# stairs_control_schematic.net
KiCad netlist of a schematic drawn in Altium Designer
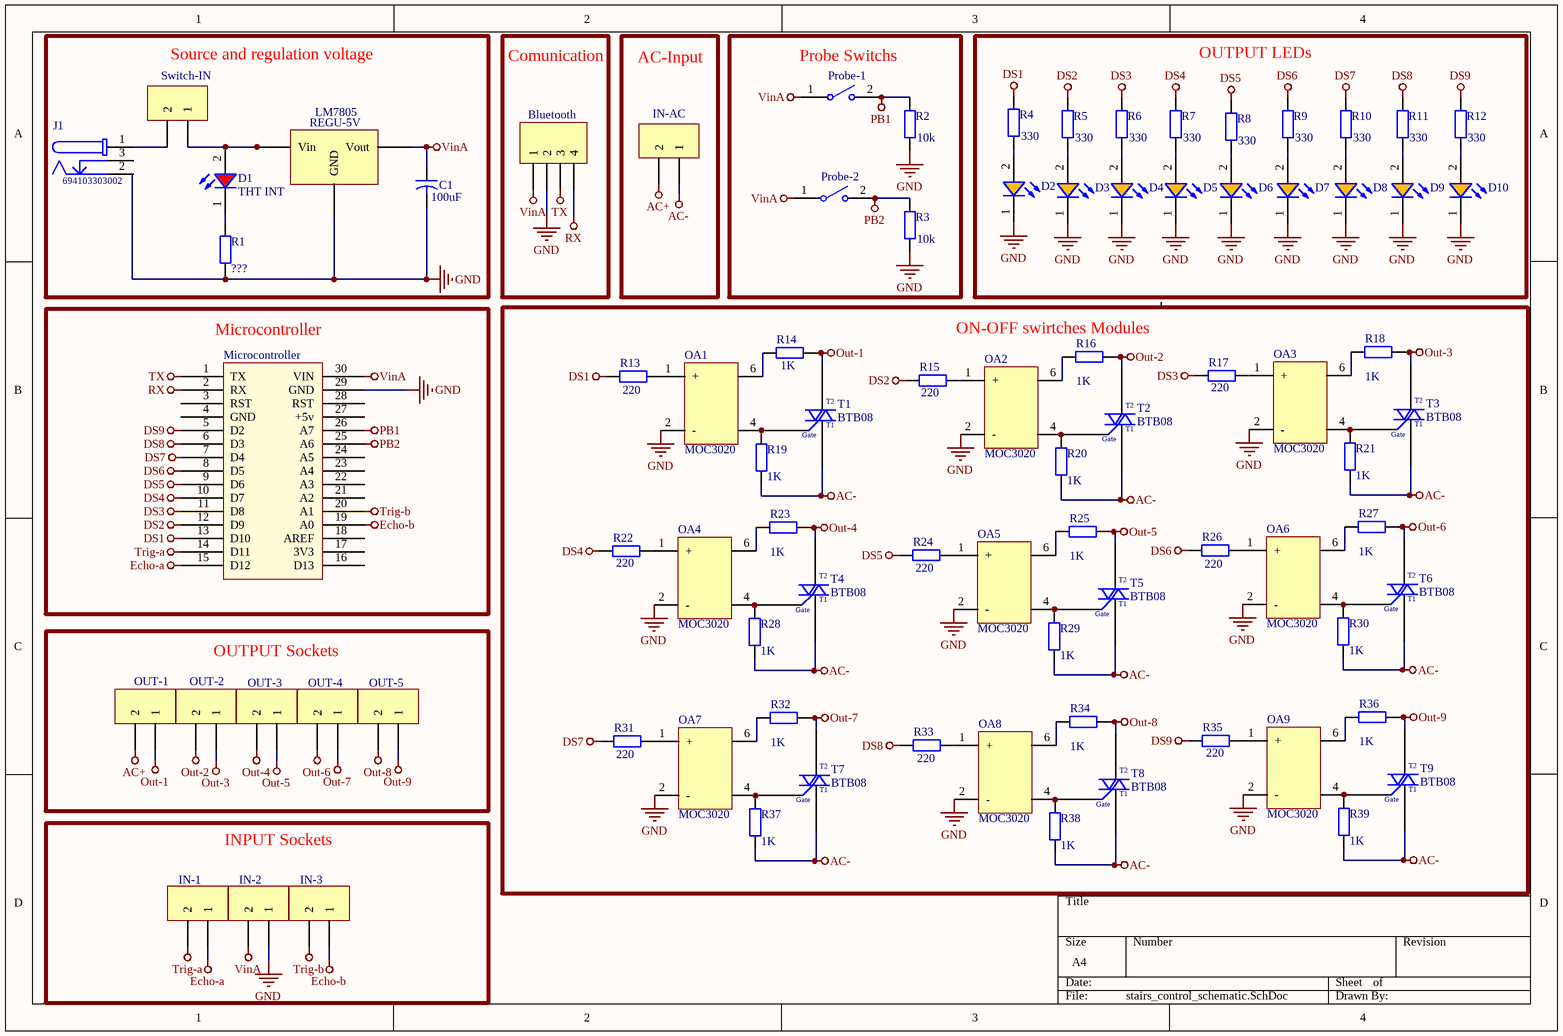
[diagram p0: stairs_control_schematic.SchDoc]

(export (version "E")
  (design (tool "Eeschema 10.0.6"))
  (components
    (comp (ref "Bluetooth")
      (value "Bluetooth")
      (footprint "HDR1X4")
      (description "Header, 4-Pin")
      (fields (field (name "PUBLISHER") "Altium Limited"))
      (libsource (lib "Miscellaneous Connectors") (part "Header 4"))
    )
    (comp (ref "C1")
      (value "100uF")
      (footprint "CAPR5-4X5")
      (description "Capacitor")
      (fields (field (name "PUBLISHER") "Altium Limited"))
      (libsource (lib "Miscellaneous Devices") (part "Cap2"))
    )
    (comp (ref "D1")
      (value "THT INT")
      (footprint "WL-TMRC_3mm")
      (description "WL-TMRC THT Mono-color Round Color, size 3mm, Super Red, 2V, 40deg")
      (fields (field (name "PART NUMBER") "151031SS04000") (field (name "PUBLISHER") "Wurth Elektronik"))
      (libsource (lib "LED THT") (part "151031SS04000"))
    )
    (comp (ref "D2")
      (value "SMD")
      (footprint "WL-SMCW_0603_H=0.7mm")
      (description "WL-SMCW SMT Mono-color Chip LED Waterclear, size 0603, Amber, 2V, 140deg")
      (fields (field (name "PART NUMBER") "150060AS75000") (field (name "PUBLISHER") "Wurth Elektronik"))
      (libsource (lib "LED'sSMD") (part "150060AS75000"))
    )
    (comp (ref "D3")
      (value "SMD")
      (footprint "WL-SMCW_0603_H=0.7mm")
      (description "WL-SMCW SMT Mono-color Chip LED Waterclear, size 0603, Amber, 2V, 140deg")
      (fields (field (name "PART NUMBER") "150060AS75000") (field (name "PUBLISHER") "Wurth Elektronik"))
      (libsource (lib "LED'sSMD") (part "150060AS75000"))
    )
    (comp (ref "D4")
      (value "SMD")
      (footprint "WL-SMCW_0603_H=0.7mm")
      (description "WL-SMCW SMT Mono-color Chip LED Waterclear, size 0603, Amber, 2V, 140deg")
      (fields (field (name "PART NUMBER") "150060AS75000") (field (name "PUBLISHER") "Wurth Elektronik"))
      (libsource (lib "LED'sSMD") (part "150060AS75000"))
    )
    (comp (ref "D5")
      (value "SMD")
      (footprint "WL-SMCW_0603_H=0.7mm")
      (description "WL-SMCW SMT Mono-color Chip LED Waterclear, size 0603, Amber, 2V, 140deg")
      (fields (field (name "PART NUMBER") "150060AS75000") (field (name "PUBLISHER") "Wurth Elektronik"))
      (libsource (lib "LED'sSMD") (part "150060AS75000"))
    )
    (comp (ref "D6")
      (value "SMD")
      (footprint "WL-SMCW_0603_H=0.7mm")
      (description "WL-SMCW SMT Mono-color Chip LED Waterclear, size 0603, Amber, 2V, 140deg")
      (fields (field (name "PART NUMBER") "150060AS75000") (field (name "PUBLISHER") "Wurth Elektronik"))
      (libsource (lib "LED'sSMD") (part "150060AS75000"))
    )
    (comp (ref "D7")
      (value "SMD")
      (footprint "WL-SMCW_0603_H=0.7mm")
      (description "WL-SMCW SMT Mono-color Chip LED Waterclear, size 0603, Amber, 2V, 140deg")
      (fields (field (name "PART NUMBER") "150060AS75000") (field (name "PUBLISHER") "Wurth Elektronik"))
      (libsource (lib "LED'sSMD") (part "150060AS75000"))
    )
    (comp (ref "D8")
      (value "SMD")
      (footprint "WL-SMCW_0603_H=0.7mm")
      (description "WL-SMCW SMT Mono-color Chip LED Waterclear, size 0603, Amber, 2V, 140deg")
      (fields (field (name "PART NUMBER") "150060AS75000") (field (name "PUBLISHER") "Wurth Elektronik"))
      (libsource (lib "LED'sSMD") (part "150060AS75000"))
    )
    (comp (ref "D9")
      (value "SMD")
      (footprint "WL-SMCW_0603_H=0.7mm")
      (description "WL-SMCW SMT Mono-color Chip LED Waterclear, size 0603, Amber, 2V, 140deg")
      (fields (field (name "PART NUMBER") "150060AS75000") (field (name "PUBLISHER") "Wurth Elektronik"))
      (libsource (lib "LED'sSMD") (part "150060AS75000"))
    )
    (comp (ref "D10")
      (value "SMD")
      (footprint "WL-SMCW_0603_H=0.7mm")
      (description "WL-SMCW SMT Mono-color Chip LED Waterclear, size 0603, Amber, 2V, 140deg")
      (fields (field (name "PART NUMBER") "150060AS75000") (field (name "PUBLISHER") "Wurth Elektronik"))
      (libsource (lib "LED'sSMD") (part "150060AS75000"))
    )
    (comp (ref "IN-1")
      (value "Terminal Block 2")
      (footprint "Terminal Block 2")
      (libsource (lib "Patrick's Library") (part "TB2"))
    )
    (comp (ref "IN-2")
      (value "Terminal Block 2")
      (footprint "Terminal Block 2")
      (libsource (lib "Patrick's Library") (part "TB2"))
    )
    (comp (ref "IN-3")
      (value "Terminal Block 2")
      (footprint "Terminal Block 2")
      (libsource (lib "Patrick's Library") (part "TB2"))
    )
    (comp (ref "IN-AC")
      (value "Terminal Block 2")
      (footprint "Terminal Block 2")
      (libsource (lib "Patrick's Library") (part "TB2"))
    )
    (comp (ref "J1")
      (value "694103303002")
      (footprint "694103303002")
      (description "DC Power Jack Connector WR-DC, Male, Right Angled, THT, 2 A, 30 V")
      (fields (field (name "PUBLISHER") "Wurth Elektronik"))
      (libsource (lib "DC_POWER_JACK_CONNECTORS_rev18b") (part "694103303002"))
    )
    (comp (ref "Microcontroller")
      (value "ArduinoNano")
      (footprint "ArduinoNano")
      (description "Arduino nano chino")
      (libsource (lib "Patrick's Library") (part "ArduinoNano"))
    )
    (comp (ref "OA1")
      (value "MOC3020")
      (footprint "PCBComponent_1")
      (libsource (lib "Patrick's Library") (part "MOC3020"))
    )
    (comp (ref "OA2")
      (value "MOC3020")
      (footprint "PCBComponent_1")
      (libsource (lib "Patrick's Library") (part "MOC3020"))
    )
    (comp (ref "OA3")
      (value "MOC3020")
      (footprint "PCBComponent_1")
      (libsource (lib "Patrick's Library") (part "MOC3020"))
    )
    (comp (ref "OA4")
      (value "MOC3020")
      (footprint "PCBComponent_1")
      (libsource (lib "Patrick's Library") (part "MOC3020"))
    )
    (comp (ref "OA5")
      (value "MOC3020")
      (footprint "PCBComponent_1")
      (libsource (lib "Patrick's Library") (part "MOC3020"))
    )
    (comp (ref "OA6")
      (value "MOC3020")
      (footprint "PCBComponent_1")
      (libsource (lib "Patrick's Library") (part "MOC3020"))
    )
    (comp (ref "OA7")
      (value "MOC3020")
      (footprint "PCBComponent_1")
      (libsource (lib "Patrick's Library") (part "MOC3020"))
    )
    (comp (ref "OA8")
      (value "MOC3020")
      (footprint "PCBComponent_1")
      (libsource (lib "Patrick's Library") (part "MOC3020"))
    )
    (comp (ref "OA9")
      (value "MOC3020")
      (footprint "PCBComponent_1")
      (libsource (lib "Patrick's Library") (part "MOC3020"))
    )
    (comp (ref "OUT-1")
      (value "Terminal Block 2")
      (footprint "Terminal Block 2")
      (libsource (lib "Patrick's Library") (part "TB2"))
    )
    (comp (ref "OUT-2")
      (value "Terminal Block 2")
      (footprint "Terminal Block 2")
      (libsource (lib "Patrick's Library") (part "TB2"))
    )
    (comp (ref "OUT-3")
      (value "Terminal Block 2")
      (footprint "Terminal Block 2")
      (libsource (lib "Patrick's Library") (part "TB2"))
    )
    (comp (ref "OUT-4")
      (value "Terminal Block 2")
      (footprint "Terminal Block 2")
      (libsource (lib "Patrick's Library") (part "TB2"))
    )
    (comp (ref "OUT-5")
      (value "Terminal Block 2")
      (footprint "Terminal Block 2")
      (libsource (lib "Patrick's Library") (part "TB2"))
    )
    (comp (ref "Probe-1")
      (value "Probe-1")
      (footprint "434111043826")
      (description "WS-TASV SMT Tact Switch 6x3.5mm, height 4.3mm, 260gf")
      (fields (field (name "PART NUMBER") "434111043826") (field (name "PUBLISHER") "Wurth Elektronik"))
      (libsource (lib "Switch SMD") (part "434111043826"))
    )
    (comp (ref "Probe-2")
      (value "Probre-2")
      (footprint "434111043826")
      (description "WS-TASV SMT Tact Switch 6x3.5mm, height 4.3mm, 260gf")
      (fields (field (name "PART NUMBER") "434111043826") (field (name "PUBLISHER") "Wurth Elektronik"))
      (libsource (lib "Switch SMD") (part "434111043826"))
    )
    (comp (ref "R1")
      (value "???")
      (footprint "AXIAL-0.4")
      (description "Resistor")
      (fields (field (name "Comment") "Res2") (field (name "PUBLISHER") "Altium Limited"))
      (libsource (lib "Miscellaneous Devices") (part "Res2"))
    )
    (comp (ref "R2")
      (value "10k")
      (footprint "WRIS-KSKE_0805_H=0.6mm")
      (description "WRIS-KSKE Thick Film Resistors, size 0805, 0.1Ohm, +/-1%, 0.33W")
      (fields (field (name "PART NUMBER") "560050320001") (field (name "PUBLISHER") "Wurth Elektronik"))
      (libsource (lib "Resistors SMD") (part "560050320001"))
    )
    (comp (ref "R3")
      (value "10k")
      (footprint "WRIS-KSKE_0805_H=0.6mm")
      (description "WRIS-KSKE Thick Film Resistors, size 0805, 0.1Ohm, +/-1%, 0.33W")
      (fields (field (name "PART NUMBER") "560050320001") (field (name "PUBLISHER") "Wurth Elektronik"))
      (libsource (lib "Resistors SMD") (part "560050320001"))
    )
    (comp (ref "R4")
      (value "330")
      (footprint "WRIS-KSKE_0805_H=0.6mm")
      (description "WRIS-KSKE Thick Film Resistors, size 0805, 0.1Ohm, +/-1%, 0.33W")
      (fields (field (name "PART NUMBER") "560050320001") (field (name "PUBLISHER") "Wurth Elektronik"))
      (libsource (lib "Resistors SMD") (part "560050320001"))
    )
    (comp (ref "R5")
      (value "330")
      (footprint "WRIS-KSKE_0805_H=0.6mm")
      (description "WRIS-KSKE Thick Film Resistors, size 0805, 0.1Ohm, +/-1%, 0.33W")
      (fields (field (name "PART NUMBER") "560050320001") (field (name "PUBLISHER") "Wurth Elektronik"))
      (libsource (lib "Resistors SMD") (part "560050320001"))
    )
    (comp (ref "R6")
      (value "330")
      (footprint "WRIS-KSKE_0805_H=0.6mm")
      (description "WRIS-KSKE Thick Film Resistors, size 0805, 0.1Ohm, +/-1%, 0.33W")
      (fields (field (name "PART NUMBER") "560050320001") (field (name "PUBLISHER") "Wurth Elektronik"))
      (libsource (lib "Resistors SMD") (part "560050320001"))
    )
    (comp (ref "R7")
      (value "330")
      (footprint "WRIS-KSKE_0805_H=0.6mm")
      (description "WRIS-KSKE Thick Film Resistors, size 0805, 0.1Ohm, +/-1%, 0.33W")
      (fields (field (name "PART NUMBER") "560050320001") (field (name "PUBLISHER") "Wurth Elektronik"))
      (libsource (lib "Resistors SMD") (part "560050320001"))
    )
    (comp (ref "R8")
      (value "330")
      (footprint "WRIS-KSKE_0805_H=0.6mm")
      (description "WRIS-KSKE Thick Film Resistors, size 0805, 0.1Ohm, +/-1%, 0.33W")
      (fields (field (name "PART NUMBER") "560050320001") (field (name "PUBLISHER") "Wurth Elektronik"))
      (libsource (lib "Resistors SMD") (part "560050320001"))
    )
    (comp (ref "R9")
      (value "330")
      (footprint "WRIS-KSKE_0805_H=0.6mm")
      (description "WRIS-KSKE Thick Film Resistors, size 0805, 0.1Ohm, +/-1%, 0.33W")
      (fields (field (name "PART NUMBER") "560050320001") (field (name "PUBLISHER") "Wurth Elektronik"))
      (libsource (lib "Resistors SMD") (part "560050320001"))
    )
    (comp (ref "R10")
      (value "330")
      (footprint "WRIS-KSKE_0805_H=0.6mm")
      (description "WRIS-KSKE Thick Film Resistors, size 0805, 0.1Ohm, +/-1%, 0.33W")
      (fields (field (name "PART NUMBER") "560050320001") (field (name "PUBLISHER") "Wurth Elektronik"))
      (libsource (lib "Resistors SMD") (part "560050320001"))
    )
    (comp (ref "R11")
      (value "330")
      (footprint "WRIS-KSKE_0805_H=0.6mm")
      (description "WRIS-KSKE Thick Film Resistors, size 0805, 0.1Ohm, +/-1%, 0.33W")
      (fields (field (name "PART NUMBER") "560050320001") (field (name "PUBLISHER") "Wurth Elektronik"))
      (libsource (lib "Resistors SMD") (part "560050320001"))
    )
    (comp (ref "R12")
      (value "330")
      (footprint "WRIS-KSKE_0805_H=0.6mm")
      (description "WRIS-KSKE Thick Film Resistors, size 0805, 0.1Ohm, +/-1%, 0.33W")
      (fields (field (name "PART NUMBER") "560050320001") (field (name "PUBLISHER") "Wurth Elektronik"))
      (libsource (lib "Resistors SMD") (part "560050320001"))
    )
    (comp (ref "R13")
      (value "220")
      (footprint "AXIAL-0.4")
      (description "Resistor")
      (fields (field (name "Comment") "Res2") (field (name "PUBLISHER") "Altium Limited"))
      (libsource (lib "") (part "Res2_1"))
    )
    (comp (ref "R14")
      (value "1K")
      (footprint "AXIAL-0.4")
      (description "Resistor")
      (fields (field (name "Comment") "Res2") (field (name "PUBLISHER") "Altium Limited"))
      (libsource (lib "") (part "Res2_2"))
    )
    (comp (ref "R15")
      (value "220")
      (footprint "AXIAL-0.4")
      (description "Resistor")
      (fields (field (name "Comment") "Res2") (field (name "PUBLISHER") "Altium Limited"))
      (libsource (lib "") (part "Res2_1"))
    )
    (comp (ref "R16")
      (value "1K")
      (footprint "AXIAL-0.4")
      (description "Resistor")
      (fields (field (name "Comment") "Res2") (field (name "PUBLISHER") "Altium Limited"))
      (libsource (lib "") (part "Res2_2"))
    )
    (comp (ref "R17")
      (value "220")
      (footprint "AXIAL-0.4")
      (description "Resistor")
      (fields (field (name "Comment") "Res2") (field (name "PUBLISHER") "Altium Limited"))
      (libsource (lib "") (part "Res2_1"))
    )
    (comp (ref "R18")
      (value "1K")
      (footprint "AXIAL-0.4")
      (description "Resistor")
      (fields (field (name "Comment") "Res2") (field (name "PUBLISHER") "Altium Limited"))
      (libsource (lib "") (part "Res2_2"))
    )
    (comp (ref "R19")
      (value "1K")
      (footprint "AXIAL-0.4")
      (description "Resistor")
      (fields (field (name "Comment") "Res2") (field (name "PUBLISHER") "Altium Limited"))
      (libsource (lib "Miscellaneous Devices") (part "Res2"))
    )
    (comp (ref "R20")
      (value "1K")
      (footprint "AXIAL-0.4")
      (description "Resistor")
      (fields (field (name "Comment") "Res2") (field (name "PUBLISHER") "Altium Limited"))
      (libsource (lib "Miscellaneous Devices") (part "Res2"))
    )
    (comp (ref "R21")
      (value "1K")
      (footprint "AXIAL-0.4")
      (description "Resistor")
      (fields (field (name "Comment") "Res2") (field (name "PUBLISHER") "Altium Limited"))
      (libsource (lib "Miscellaneous Devices") (part "Res2"))
    )
    (comp (ref "R22")
      (value "220")
      (footprint "AXIAL-0.4")
      (description "Resistor")
      (fields (field (name "Comment") "Res2") (field (name "PUBLISHER") "Altium Limited"))
      (libsource (lib "") (part "Res2_1"))
    )
    (comp (ref "R23")
      (value "1K")
      (footprint "AXIAL-0.4")
      (description "Resistor")
      (fields (field (name "Comment") "Res2") (field (name "PUBLISHER") "Altium Limited"))
      (libsource (lib "") (part "Res2_2"))
    )
    (comp (ref "R24")
      (value "220")
      (footprint "AXIAL-0.4")
      (description "Resistor")
      (fields (field (name "Comment") "Res2") (field (name "PUBLISHER") "Altium Limited"))
      (libsource (lib "") (part "Res2_1"))
    )
    (comp (ref "R25")
      (value "1K")
      (footprint "AXIAL-0.4")
      (description "Resistor")
      (fields (field (name "Comment") "Res2") (field (name "PUBLISHER") "Altium Limited"))
      (libsource (lib "") (part "Res2_2"))
    )
    (comp (ref "R26")
      (value "220")
      (footprint "AXIAL-0.4")
      (description "Resistor")
      (fields (field (name "Comment") "Res2") (field (name "PUBLISHER") "Altium Limited"))
      (libsource (lib "") (part "Res2_1"))
    )
    (comp (ref "R27")
      (value "1K")
      (footprint "AXIAL-0.4")
      (description "Resistor")
      (fields (field (name "Comment") "Res2") (field (name "PUBLISHER") "Altium Limited"))
      (libsource (lib "") (part "Res2_2"))
    )
    (comp (ref "R28")
      (value "1K")
      (footprint "AXIAL-0.4")
      (description "Resistor")
      (fields (field (name "Comment") "Res2") (field (name "PUBLISHER") "Altium Limited"))
      (libsource (lib "Miscellaneous Devices") (part "Res2"))
    )
    (comp (ref "R29")
      (value "1K")
      (footprint "AXIAL-0.4")
      (description "Resistor")
      (fields (field (name "Comment") "Res2") (field (name "PUBLISHER") "Altium Limited"))
      (libsource (lib "Miscellaneous Devices") (part "Res2"))
    )
    (comp (ref "R30")
      (value "1K")
      (footprint "AXIAL-0.4")
      (description "Resistor")
      (fields (field (name "Comment") "Res2") (field (name "PUBLISHER") "Altium Limited"))
      (libsource (lib "Miscellaneous Devices") (part "Res2"))
    )
    (comp (ref "R31")
      (value "220")
      (footprint "AXIAL-0.4")
      (description "Resistor")
      (fields (field (name "Comment") "Res2") (field (name "PUBLISHER") "Altium Limited"))
      (libsource (lib "") (part "Res2_1"))
    )
    (comp (ref "R32")
      (value "1K")
      (footprint "AXIAL-0.4")
      (description "Resistor")
      (fields (field (name "Comment") "Res2") (field (name "PUBLISHER") "Altium Limited"))
      (libsource (lib "") (part "Res2_2"))
    )
    (comp (ref "R33")
      (value "220")
      (footprint "AXIAL-0.4")
      (description "Resistor")
      (fields (field (name "Comment") "Res2") (field (name "PUBLISHER") "Altium Limited"))
      (libsource (lib "") (part "Res2_1"))
    )
    (comp (ref "R34")
      (value "1K")
      (footprint "AXIAL-0.4")
      (description "Resistor")
      (fields (field (name "Comment") "Res2") (field (name "PUBLISHER") "Altium Limited"))
      (libsource (lib "") (part "Res2_2"))
    )
    (comp (ref "R35")
      (value "220")
      (footprint "AXIAL-0.4")
      (description "Resistor")
      (fields (field (name "Comment") "Res2") (field (name "PUBLISHER") "Altium Limited"))
      (libsource (lib "") (part "Res2_1"))
    )
    (comp (ref "R36")
      (value "1K")
      (footprint "AXIAL-0.4")
      (description "Resistor")
      (fields (field (name "Comment") "Res2") (field (name "PUBLISHER") "Altium Limited"))
      (libsource (lib "") (part "Res2_2"))
    )
    (comp (ref "R37")
      (value "1K")
      (footprint "AXIAL-0.4")
      (description "Resistor")
      (fields (field (name "Comment") "Res2") (field (name "PUBLISHER") "Altium Limited"))
      (libsource (lib "Miscellaneous Devices") (part "Res2"))
    )
    (comp (ref "R38")
      (value "1K")
      (footprint "AXIAL-0.4")
      (description "Resistor")
      (fields (field (name "Comment") "Res2") (field (name "PUBLISHER") "Altium Limited"))
      (libsource (lib "Miscellaneous Devices") (part "Res2"))
    )
    (comp (ref "R39")
      (value "1K")
      (footprint "AXIAL-0.4")
      (description "Resistor")
      (fields (field (name "Comment") "Res2") (field (name "PUBLISHER") "Altium Limited"))
      (libsource (lib "Miscellaneous Devices") (part "Res2"))
    )
    (comp (ref "REGU-5V")
      (value "LM7805")
      (footprint "LM7805")
      (libsource (lib "Patrick's Library") (part "LM7805"))
    )
    (comp (ref "Switch-IN")
      (value "Terminal Block 2")
      (footprint "Terminal Block 2")
      (libsource (lib "Patrick's Library") (part "TB2"))
    )
    (comp (ref "T1")
      (value "BTB08")
      (footprint "LM7805")
      (libsource (lib "Patrick's Library") (part "BTB08"))
    )
    (comp (ref "T2")
      (value "BTB08")
      (footprint "LM7805")
      (libsource (lib "Patrick's Library") (part "BTB08"))
    )
    (comp (ref "T3")
      (value "BTB08")
      (footprint "LM7805")
      (libsource (lib "Patrick's Library") (part "BTB08"))
    )
    (comp (ref "T4")
      (value "BTB08")
      (footprint "LM7805")
      (libsource (lib "Patrick's Library") (part "BTB08"))
    )
    (comp (ref "T5")
      (value "BTB08")
      (footprint "LM7805")
      (libsource (lib "Patrick's Library") (part "BTB08"))
    )
    (comp (ref "T6")
      (value "BTB08")
      (footprint "LM7805")
      (libsource (lib "Patrick's Library") (part "BTB08"))
    )
    (comp (ref "T7")
      (value "BTB08")
      (footprint "LM7805")
      (libsource (lib "Patrick's Library") (part "BTB08"))
    )
    (comp (ref "T8")
      (value "BTB08")
      (footprint "LM7805")
      (libsource (lib "Patrick's Library") (part "BTB08"))
    )
    (comp (ref "T9")
      (value "BTB08")
      (footprint "LM7805")
      (libsource (lib "Patrick's Library") (part "BTB08"))
    )
  )
  (nets
    (net (code "1") (name "AC+") (class "Default")
      (node (ref "IN-AC") (pin "2") (pinfunction "2_2") (pintype "passive"))
      (node (ref "OUT-1") (pin "2") (pinfunction "2_2") (pintype "passive"))
    )
    (net (code "2") (name "AC-") (class "Default")
      (node (ref "IN-AC") (pin "1") (pinfunction "1_1") (pintype "passive"))
      (node (ref "R19") (pin "1") (pinfunction "1_1") (pintype "passive"))
      (node (ref "R20") (pin "1") (pinfunction "1_1") (pintype "passive"))
      (node (ref "R21") (pin "1") (pinfunction "1_1") (pintype "passive"))
      (node (ref "R28") (pin "1") (pinfunction "1_1") (pintype "passive"))
      (node (ref "R29") (pin "1") (pinfunction "1_1") (pintype "passive"))
      (node (ref "R30") (pin "1") (pinfunction "1_1") (pintype "passive"))
      (node (ref "R37") (pin "1") (pinfunction "1_1") (pintype "passive"))
      (node (ref "R38") (pin "1") (pinfunction "1_1") (pintype "passive"))
      (node (ref "R39") (pin "1") (pinfunction "1_1") (pintype "passive"))
      (node (ref "T1") (pin "1") (pinfunction "T1_1") (pintype "passive"))
      (node (ref "T2") (pin "1") (pinfunction "T1_1") (pintype "passive"))
      (node (ref "T3") (pin "1") (pinfunction "T1_1") (pintype "passive"))
      (node (ref "T4") (pin "1") (pinfunction "T1_1") (pintype "passive"))
      (node (ref "T5") (pin "1") (pinfunction "T1_1") (pintype "passive"))
      (node (ref "T6") (pin "1") (pinfunction "T1_1") (pintype "passive"))
      (node (ref "T7") (pin "1") (pinfunction "T1_1") (pintype "passive"))
      (node (ref "T8") (pin "1") (pinfunction "T1_1") (pintype "passive"))
      (node (ref "T9") (pin "1") (pinfunction "T1_1") (pintype "passive"))
    )
    (net (code "3") (name "DS1") (class "Default")
      (node (ref "Microcontroller") (pin "13") (pinfunction "D10_13") (pintype "passive"))
      (node (ref "R13") (pin "2") (pinfunction "2_2") (pintype "passive"))
      (node (ref "R4") (pin "2") (pinfunction "2_2") (pintype "passive"))
    )
    (net (code "4") (name "DS2") (class "Default")
      (node (ref "Microcontroller") (pin "12") (pinfunction "D9_12") (pintype "passive"))
      (node (ref "R15") (pin "2") (pinfunction "2_2") (pintype "passive"))
      (node (ref "R5") (pin "2") (pinfunction "2_2") (pintype "passive"))
    )
    (net (code "5") (name "DS3") (class "Default")
      (node (ref "Microcontroller") (pin "11") (pinfunction "D8_11") (pintype "passive"))
      (node (ref "R17") (pin "2") (pinfunction "2_2") (pintype "passive"))
      (node (ref "R6") (pin "2") (pinfunction "2_2") (pintype "passive"))
    )
    (net (code "6") (name "DS4") (class "Default")
      (node (ref "Microcontroller") (pin "10") (pinfunction "D7_10") (pintype "passive"))
      (node (ref "R22") (pin "2") (pinfunction "2_2") (pintype "passive"))
      (node (ref "R7") (pin "2") (pinfunction "2_2") (pintype "passive"))
    )
    (net (code "7") (name "DS5") (class "Default")
      (node (ref "Microcontroller") (pin "9") (pinfunction "D6_9") (pintype "passive"))
      (node (ref "R24") (pin "2") (pinfunction "2_2") (pintype "passive"))
      (node (ref "R8") (pin "2") (pinfunction "2_2") (pintype "passive"))
    )
    (net (code "8") (name "DS6") (class "Default")
      (node (ref "Microcontroller") (pin "8") (pinfunction "D5_8") (pintype "passive"))
      (node (ref "R26") (pin "2") (pinfunction "2_2") (pintype "passive"))
      (node (ref "R9") (pin "2") (pinfunction "2_2") (pintype "passive"))
    )
    (net (code "9") (name "DS7") (class "Default")
      (node (ref "Microcontroller") (pin "7") (pinfunction "D4_7") (pintype "passive"))
      (node (ref "R10") (pin "2") (pinfunction "2_2") (pintype "passive"))
      (node (ref "R31") (pin "2") (pinfunction "2_2") (pintype "passive"))
    )
    (net (code "10") (name "DS8") (class "Default")
      (node (ref "Microcontroller") (pin "6") (pinfunction "D3_6") (pintype "passive"))
      (node (ref "R11") (pin "2") (pinfunction "2_2") (pintype "passive"))
      (node (ref "R33") (pin "2") (pinfunction "2_2") (pintype "passive"))
    )
    (net (code "11") (name "DS9") (class "Default")
      (node (ref "Microcontroller") (pin "5") (pinfunction "D2_5") (pintype "passive"))
      (node (ref "R12") (pin "2") (pinfunction "2_2") (pintype "passive"))
      (node (ref "R35") (pin "2") (pinfunction "2_2") (pintype "passive"))
    )
    (net (code "12") (name "Echo-a") (class "Default")
      (node (ref "IN-1") (pin "1") (pinfunction "1_1") (pintype "passive"))
      (node (ref "Microcontroller") (pin "15") (pinfunction "D12_15") (pintype "passive"))
    )
    (net (code "13") (name "Echo-b") (class "Default")
      (node (ref "IN-3") (pin "1") (pinfunction "1_1") (pintype "passive"))
      (node (ref "Microcontroller") (pin "19") (pinfunction "A0_19") (pintype "passive"))
    )
    (net (code "14") (name "GND") (class "Default")
      (node (ref "Bluetooth") (pin "2") (pinfunction "2_2") (pintype "passive"))
      (node (ref "C1") (pin "2") (pinfunction "2_2") (pintype "passive"))
      (node (ref "D10") (pin "1") (pinfunction "K_1") (pintype "passive"))
      (node (ref "D2") (pin "1") (pinfunction "K_1") (pintype "passive"))
      (node (ref "D3") (pin "1") (pinfunction "K_1") (pintype "passive"))
      (node (ref "D4") (pin "1") (pinfunction "K_1") (pintype "passive"))
      (node (ref "D5") (pin "1") (pinfunction "K_1") (pintype "passive"))
      (node (ref "D6") (pin "1") (pinfunction "K_1") (pintype "passive"))
      (node (ref "D7") (pin "1") (pinfunction "K_1") (pintype "passive"))
      (node (ref "D8") (pin "1") (pinfunction "K_1") (pintype "passive"))
      (node (ref "D9") (pin "1") (pinfunction "K_1") (pintype "passive"))
      (node (ref "IN-2") (pin "1") (pinfunction "1_1") (pintype "passive"))
      (node (ref "J1") (pin "2") (pinfunction "2_2") (pintype "passive"))
      (node (ref "Microcontroller") (pin "29") (pinfunction "GND_29") (pintype "passive"))
      (node (ref "OA1") (pin "2") (pinfunction "-_2") (pintype "passive"))
      (node (ref "OA2") (pin "2") (pinfunction "-_2") (pintype "passive"))
      (node (ref "OA3") (pin "2") (pinfunction "-_2") (pintype "passive"))
      (node (ref "OA4") (pin "2") (pinfunction "-_2") (pintype "passive"))
      (node (ref "OA5") (pin "2") (pinfunction "-_2") (pintype "passive"))
      (node (ref "OA6") (pin "2") (pinfunction "-_2") (pintype "passive"))
      (node (ref "OA7") (pin "2") (pinfunction "-_2") (pintype "passive"))
      (node (ref "OA8") (pin "2") (pinfunction "-_2") (pintype "passive"))
      (node (ref "OA9") (pin "2") (pinfunction "-_2") (pintype "passive"))
      (node (ref "R1") (pin "1") (pinfunction "1_1") (pintype "passive"))
      (node (ref "R2") (pin "1") (pinfunction "1_1") (pintype "passive"))
      (node (ref "R3") (pin "1") (pinfunction "1_1") (pintype "passive"))
      (node (ref "REGU-5V") (pin "2") (pinfunction "GND_2") (pintype "passive"))
    )
    (net (code "15") (name "Net-(D1-A)") (class "Default")
      (node (ref "D1") (pin "2") (pinfunction "A_2") (pintype "passive"))
      (node (ref "REGU-5V") (pin "1") (pinfunction "Vin_1") (pintype "passive"))
      (node (ref "Switch-IN") (pin "1") (pinfunction "1_1") (pintype "passive"))
    )
    (net (code "16") (name "Net-(D1-K)") (class "Default")
      (node (ref "D1") (pin "1") (pinfunction "K_1") (pintype "passive"))
      (node (ref "R1") (pin "2") (pinfunction "2_2") (pintype "passive"))
    )
    (net (code "17") (name "Net-(D2-A)") (class "Default")
      (node (ref "D2") (pin "2") (pinfunction "A_2") (pintype "passive"))
      (node (ref "R4") (pin "1") (pinfunction "1_1") (pintype "passive"))
    )
    (net (code "18") (name "Net-(D3-A)") (class "Default")
      (node (ref "D3") (pin "2") (pinfunction "A_2") (pintype "passive"))
      (node (ref "R5") (pin "1") (pinfunction "1_1") (pintype "passive"))
    )
    (net (code "19") (name "Net-(D4-A)") (class "Default")
      (node (ref "D4") (pin "2") (pinfunction "A_2") (pintype "passive"))
      (node (ref "R6") (pin "1") (pinfunction "1_1") (pintype "passive"))
    )
    (net (code "20") (name "Net-(D5-A)") (class "Default")
      (node (ref "D5") (pin "2") (pinfunction "A_2") (pintype "passive"))
      (node (ref "R7") (pin "1") (pinfunction "1_1") (pintype "passive"))
    )
    (net (code "21") (name "Net-(D6-A)") (class "Default")
      (node (ref "D6") (pin "2") (pinfunction "A_2") (pintype "passive"))
      (node (ref "R8") (pin "1") (pinfunction "1_1") (pintype "passive"))
    )
    (net (code "22") (name "Net-(D7-A)") (class "Default")
      (node (ref "D7") (pin "2") (pinfunction "A_2") (pintype "passive"))
      (node (ref "R9") (pin "1") (pinfunction "1_1") (pintype "passive"))
    )
    (net (code "23") (name "Net-(D8-A)") (class "Default")
      (node (ref "D8") (pin "2") (pinfunction "A_2") (pintype "passive"))
      (node (ref "R10") (pin "1") (pinfunction "1_1") (pintype "passive"))
    )
    (net (code "24") (name "Net-(D9-A)") (class "Default")
      (node (ref "D9") (pin "2") (pinfunction "A_2") (pintype "passive"))
      (node (ref "R11") (pin "1") (pinfunction "1_1") (pintype "passive"))
    )
    (net (code "25") (name "Net-(D10-A)") (class "Default")
      (node (ref "D10") (pin "2") (pinfunction "A_2") (pintype "passive"))
      (node (ref "R12") (pin "1") (pinfunction "1_1") (pintype "passive"))
    )
    (net (code "26") (name "Net-(J1-Pad1)") (class "Default")
      (node (ref "J1") (pin "1") (pinfunction "1_1") (pintype "passive"))
      (node (ref "Switch-IN") (pin "2") (pinfunction "2_2") (pintype "passive"))
    )
    (net (code "27") (name "Net-(OA1-+)") (class "Default")
      (node (ref "OA1") (pin "1") (pinfunction "+_1") (pintype "passive"))
      (node (ref "R13") (pin "1") (pinfunction "1_1") (pintype "passive"))
    )
    (net (code "28") (name "Net-(OA1-50)") (class "Default")
      (node (ref "OA1") (pin "4") (pinfunction "50_4") (pintype "passive"))
      (node (ref "R19") (pin "2") (pinfunction "2_2") (pintype "passive"))
      (node (ref "T1") (pin "3") (pinfunction "Gate_3") (pintype "passive"))
    )
    (net (code "29") (name "Net-(OA1-51)") (class "Default")
      (node (ref "OA1") (pin "6") (pinfunction "51_6") (pintype "passive"))
      (node (ref "R14") (pin "1") (pinfunction "1_1") (pintype "passive"))
    )
    (net (code "30") (name "Net-(OA2-+)") (class "Default")
      (node (ref "OA2") (pin "1") (pinfunction "+_1") (pintype "passive"))
      (node (ref "R15") (pin "1") (pinfunction "1_1") (pintype "passive"))
    )
    (net (code "31") (name "Net-(OA2-50)") (class "Default")
      (node (ref "OA2") (pin "4") (pinfunction "50_4") (pintype "passive"))
      (node (ref "R20") (pin "2") (pinfunction "2_2") (pintype "passive"))
      (node (ref "T2") (pin "3") (pinfunction "Gate_3") (pintype "passive"))
    )
    (net (code "32") (name "Net-(OA2-51)") (class "Default")
      (node (ref "OA2") (pin "6") (pinfunction "51_6") (pintype "passive"))
      (node (ref "R16") (pin "1") (pinfunction "1_1") (pintype "passive"))
    )
    (net (code "33") (name "Net-(OA3-+)") (class "Default")
      (node (ref "OA3") (pin "1") (pinfunction "+_1") (pintype "passive"))
      (node (ref "R17") (pin "1") (pinfunction "1_1") (pintype "passive"))
    )
    (net (code "34") (name "Net-(OA3-50)") (class "Default")
      (node (ref "OA3") (pin "4") (pinfunction "50_4") (pintype "passive"))
      (node (ref "R21") (pin "2") (pinfunction "2_2") (pintype "passive"))
      (node (ref "T3") (pin "3") (pinfunction "Gate_3") (pintype "passive"))
    )
    (net (code "35") (name "Net-(OA3-51)") (class "Default")
      (node (ref "OA3") (pin "6") (pinfunction "51_6") (pintype "passive"))
      (node (ref "R18") (pin "1") (pinfunction "1_1") (pintype "passive"))
    )
    (net (code "36") (name "Net-(OA4-+)") (class "Default")
      (node (ref "OA4") (pin "1") (pinfunction "+_1") (pintype "passive"))
      (node (ref "R22") (pin "1") (pinfunction "1_1") (pintype "passive"))
    )
    (net (code "37") (name "Net-(OA4-50)") (class "Default")
      (node (ref "OA4") (pin "4") (pinfunction "50_4") (pintype "passive"))
      (node (ref "R28") (pin "2") (pinfunction "2_2") (pintype "passive"))
      (node (ref "T4") (pin "3") (pinfunction "Gate_3") (pintype "passive"))
    )
    (net (code "38") (name "Net-(OA4-51)") (class "Default")
      (node (ref "OA4") (pin "6") (pinfunction "51_6") (pintype "passive"))
      (node (ref "R23") (pin "1") (pinfunction "1_1") (pintype "passive"))
    )
    (net (code "39") (name "Net-(OA5-+)") (class "Default")
      (node (ref "OA5") (pin "1") (pinfunction "+_1") (pintype "passive"))
      (node (ref "R24") (pin "1") (pinfunction "1_1") (pintype "passive"))
    )
    (net (code "40") (name "Net-(OA5-50)") (class "Default")
      (node (ref "OA5") (pin "4") (pinfunction "50_4") (pintype "passive"))
      (node (ref "R29") (pin "2") (pinfunction "2_2") (pintype "passive"))
      (node (ref "T5") (pin "3") (pinfunction "Gate_3") (pintype "passive"))
    )
    (net (code "41") (name "Net-(OA5-51)") (class "Default")
      (node (ref "OA5") (pin "6") (pinfunction "51_6") (pintype "passive"))
      (node (ref "R25") (pin "1") (pinfunction "1_1") (pintype "passive"))
    )
    (net (code "42") (name "Net-(OA6-+)") (class "Default")
      (node (ref "OA6") (pin "1") (pinfunction "+_1") (pintype "passive"))
      (node (ref "R26") (pin "1") (pinfunction "1_1") (pintype "passive"))
    )
    (net (code "43") (name "Net-(OA6-50)") (class "Default")
      (node (ref "OA6") (pin "4") (pinfunction "50_4") (pintype "passive"))
      (node (ref "R30") (pin "2") (pinfunction "2_2") (pintype "passive"))
      (node (ref "T6") (pin "3") (pinfunction "Gate_3") (pintype "passive"))
    )
    (net (code "44") (name "Net-(OA6-51)") (class "Default")
      (node (ref "OA6") (pin "6") (pinfunction "51_6") (pintype "passive"))
      (node (ref "R27") (pin "1") (pinfunction "1_1") (pintype "passive"))
    )
    (net (code "45") (name "Net-(OA7-+)") (class "Default")
      (node (ref "OA7") (pin "1") (pinfunction "+_1") (pintype "passive"))
      (node (ref "R31") (pin "1") (pinfunction "1_1") (pintype "passive"))
    )
    (net (code "46") (name "Net-(OA7-50)") (class "Default")
      (node (ref "OA7") (pin "4") (pinfunction "50_4") (pintype "passive"))
      (node (ref "R37") (pin "2") (pinfunction "2_2") (pintype "passive"))
      (node (ref "T7") (pin "3") (pinfunction "Gate_3") (pintype "passive"))
    )
    (net (code "47") (name "Net-(OA7-51)") (class "Default")
      (node (ref "OA7") (pin "6") (pinfunction "51_6") (pintype "passive"))
      (node (ref "R32") (pin "1") (pinfunction "1_1") (pintype "passive"))
    )
    (net (code "48") (name "Net-(OA8-+)") (class "Default")
      (node (ref "OA8") (pin "1") (pinfunction "+_1") (pintype "passive"))
      (node (ref "R33") (pin "1") (pinfunction "1_1") (pintype "passive"))
    )
    (net (code "49") (name "Net-(OA8-50)") (class "Default")
      (node (ref "OA8") (pin "4") (pinfunction "50_4") (pintype "passive"))
      (node (ref "R38") (pin "2") (pinfunction "2_2") (pintype "passive"))
      (node (ref "T8") (pin "3") (pinfunction "Gate_3") (pintype "passive"))
    )
    (net (code "50") (name "Net-(OA8-51)") (class "Default")
      (node (ref "OA8") (pin "6") (pinfunction "51_6") (pintype "passive"))
      (node (ref "R34") (pin "1") (pinfunction "1_1") (pintype "passive"))
    )
    (net (code "51") (name "Net-(OA9-+)") (class "Default")
      (node (ref "OA9") (pin "1") (pinfunction "+_1") (pintype "passive"))
      (node (ref "R35") (pin "1") (pinfunction "1_1") (pintype "passive"))
    )
    (net (code "52") (name "Net-(OA9-50)") (class "Default")
      (node (ref "OA9") (pin "4") (pinfunction "50_4") (pintype "passive"))
      (node (ref "R39") (pin "2") (pinfunction "2_2") (pintype "passive"))
      (node (ref "T9") (pin "3") (pinfunction "Gate_3") (pintype "passive"))
    )
    (net (code "53") (name "Net-(OA9-51)") (class "Default")
      (node (ref "OA9") (pin "6") (pinfunction "51_6") (pintype "passive"))
      (node (ref "R36") (pin "1") (pinfunction "1_1") (pintype "passive"))
    )
    (net (code "54") (name "Out-1") (class "Default")
      (node (ref "OUT-1") (pin "1") (pinfunction "1_1") (pintype "passive"))
      (node (ref "R14") (pin "2") (pinfunction "2_2") (pintype "passive"))
      (node (ref "T1") (pin "2") (pinfunction "T2_2") (pintype "passive"))
    )
    (net (code "55") (name "Out-2") (class "Default")
      (node (ref "OUT-2") (pin "2") (pinfunction "2_2") (pintype "passive"))
      (node (ref "R16") (pin "2") (pinfunction "2_2") (pintype "passive"))
      (node (ref "T2") (pin "2") (pinfunction "T2_2") (pintype "passive"))
    )
    (net (code "56") (name "Out-3") (class "Default")
      (node (ref "OUT-2") (pin "1") (pinfunction "1_1") (pintype "passive"))
      (node (ref "R18") (pin "2") (pinfunction "2_2") (pintype "passive"))
      (node (ref "T3") (pin "2") (pinfunction "T2_2") (pintype "passive"))
    )
    (net (code "57") (name "Out-4") (class "Default")
      (node (ref "OUT-3") (pin "2") (pinfunction "2_2") (pintype "passive"))
      (node (ref "R23") (pin "2") (pinfunction "2_2") (pintype "passive"))
      (node (ref "T4") (pin "2") (pinfunction "T2_2") (pintype "passive"))
    )
    (net (code "58") (name "Out-5") (class "Default")
      (node (ref "OUT-3") (pin "1") (pinfunction "1_1") (pintype "passive"))
      (node (ref "R25") (pin "2") (pinfunction "2_2") (pintype "passive"))
      (node (ref "T5") (pin "2") (pinfunction "T2_2") (pintype "passive"))
    )
    (net (code "59") (name "Out-6") (class "Default")
      (node (ref "OUT-4") (pin "2") (pinfunction "2_2") (pintype "passive"))
      (node (ref "R27") (pin "2") (pinfunction "2_2") (pintype "passive"))
      (node (ref "T6") (pin "2") (pinfunction "T2_2") (pintype "passive"))
    )
    (net (code "60") (name "Out-7") (class "Default")
      (node (ref "OUT-4") (pin "1") (pinfunction "1_1") (pintype "passive"))
      (node (ref "R32") (pin "2") (pinfunction "2_2") (pintype "passive"))
      (node (ref "T7") (pin "2") (pinfunction "T2_2") (pintype "passive"))
    )
    (net (code "61") (name "Out-8") (class "Default")
      (node (ref "OUT-5") (pin "2") (pinfunction "2_2") (pintype "passive"))
      (node (ref "R34") (pin "2") (pinfunction "2_2") (pintype "passive"))
      (node (ref "T8") (pin "2") (pinfunction "T2_2") (pintype "passive"))
    )
    (net (code "62") (name "Out-9") (class "Default")
      (node (ref "OUT-5") (pin "1") (pinfunction "1_1") (pintype "passive"))
      (node (ref "R36") (pin "2") (pinfunction "2_2") (pintype "passive"))
      (node (ref "T9") (pin "2") (pinfunction "T2_2") (pintype "passive"))
    )
    (net (code "63") (name "PB1") (class "Default")
      (node (ref "Microcontroller") (pin "26") (pinfunction "A7_26") (pintype "passive"))
      (node (ref "Probe-1") (pin "2") (pinfunction "2_2") (pintype "passive"))
      (node (ref "R2") (pin "2") (pinfunction "2_2") (pintype "passive"))
    )
    (net (code "64") (name "PB2") (class "Default")
      (node (ref "Microcontroller") (pin "25") (pinfunction "A6_25") (pintype "passive"))
      (node (ref "Probe-2") (pin "2") (pinfunction "2_2") (pintype "passive"))
      (node (ref "R3") (pin "2") (pinfunction "2_2") (pintype "passive"))
    )
    (net (code "65") (name "RX") (class "Default")
      (node (ref "Bluetooth") (pin "4") (pinfunction "4_4") (pintype "passive"))
      (node (ref "Microcontroller") (pin "2") (pinfunction "RX_2") (pintype "passive"))
    )
    (net (code "66") (name "TX") (class "Default")
      (node (ref "Bluetooth") (pin "3") (pinfunction "3_3") (pintype "passive"))
      (node (ref "Microcontroller") (pin "1") (pinfunction "TX_1") (pintype "passive"))
    )
    (net (code "67") (name "Trig-a") (class "Default")
      (node (ref "IN-1") (pin "2") (pinfunction "2_2") (pintype "passive"))
      (node (ref "Microcontroller") (pin "14") (pinfunction "D11_14") (pintype "passive"))
    )
    (net (code "68") (name "Trig-b") (class "Default")
      (node (ref "IN-3") (pin "2") (pinfunction "2_2") (pintype "passive"))
      (node (ref "Microcontroller") (pin "20") (pinfunction "A1_20") (pintype "passive"))
    )
    (net (code "69") (name "VinA") (class "Default")
      (node (ref "Bluetooth") (pin "1") (pinfunction "1_1") (pintype "passive"))
      (node (ref "C1") (pin "1") (pinfunction "1_1") (pintype "passive"))
      (node (ref "IN-2") (pin "2") (pinfunction "2_2") (pintype "passive"))
      (node (ref "Microcontroller") (pin "30") (pinfunction "VIN_30") (pintype "passive"))
      (node (ref "Probe-1") (pin "1") (pinfunction "1_1") (pintype "passive"))
      (node (ref "Probe-2") (pin "1") (pinfunction "1_1") (pintype "passive"))
      (node (ref "REGU-5V") (pin "3") (pinfunction "Vout_3") (pintype "passive"))
    )
    (net (code "70") (name "unconnected-(J1-Pad3)") (class "Default")
      (node (ref "J1") (pin "3") (pinfunction "3_3") (pintype "passive"))
    )
    (net (code "71") (name "unconnected-(Microcontroller-+5v-Pad27)") (class "Default")
      (node (ref "Microcontroller") (pin "27") (pinfunction "+5v_27") (pintype "passive"))
    )
    (net (code "72") (name "unconnected-(Microcontroller-3V3-Pad17)") (class "Default")
      (node (ref "Microcontroller") (pin "17") (pinfunction "3V3_17") (pintype "passive"))
    )
    (net (code "73") (name "unconnected-(Microcontroller-A2-Pad21)") (class "Default")
      (node (ref "Microcontroller") (pin "21") (pinfunction "A2_21") (pintype "passive"))
    )
    (net (code "74") (name "unconnected-(Microcontroller-A3-Pad22)") (class "Default")
      (node (ref "Microcontroller") (pin "22") (pinfunction "A3_22") (pintype "passive"))
    )
    (net (code "75") (name "unconnected-(Microcontroller-A4-Pad23)") (class "Default")
      (node (ref "Microcontroller") (pin "23") (pinfunction "A4_23") (pintype "passive"))
    )
    (net (code "76") (name "unconnected-(Microcontroller-A5-Pad24)") (class "Default")
      (node (ref "Microcontroller") (pin "24") (pinfunction "A5_24") (pintype "passive"))
    )
    (net (code "77") (name "unconnected-(Microcontroller-AREF-Pad18)") (class "Default")
      (node (ref "Microcontroller") (pin "18") (pinfunction "AREF_18") (pintype "passive"))
    )
    (net (code "78") (name "unconnected-(Microcontroller-D13-Pad16)") (class "Default")
      (node (ref "Microcontroller") (pin "16") (pinfunction "D13_16") (pintype "passive"))
    )
    (net (code "79") (name "unconnected-(Microcontroller-GND-Pad4)") (class "Default")
      (node (ref "Microcontroller") (pin "4") (pinfunction "GND_4") (pintype "passive"))
    )
    (net (code "80") (name "unconnected-(Microcontroller-RST-Pad3)") (class "Default")
      (node (ref "Microcontroller") (pin "3") (pinfunction "RST_3") (pintype "passive"))
    )
    (net (code "81") (name "unconnected-(Microcontroller-RST-Pad28)") (class "Default")
      (node (ref "Microcontroller") (pin "28") (pinfunction "RST_28") (pintype "passive"))
    )
  )
)
